# UNO-Rev3_Breakout_v10.net
KiCad netlist of a schematic drawn in EAGLE
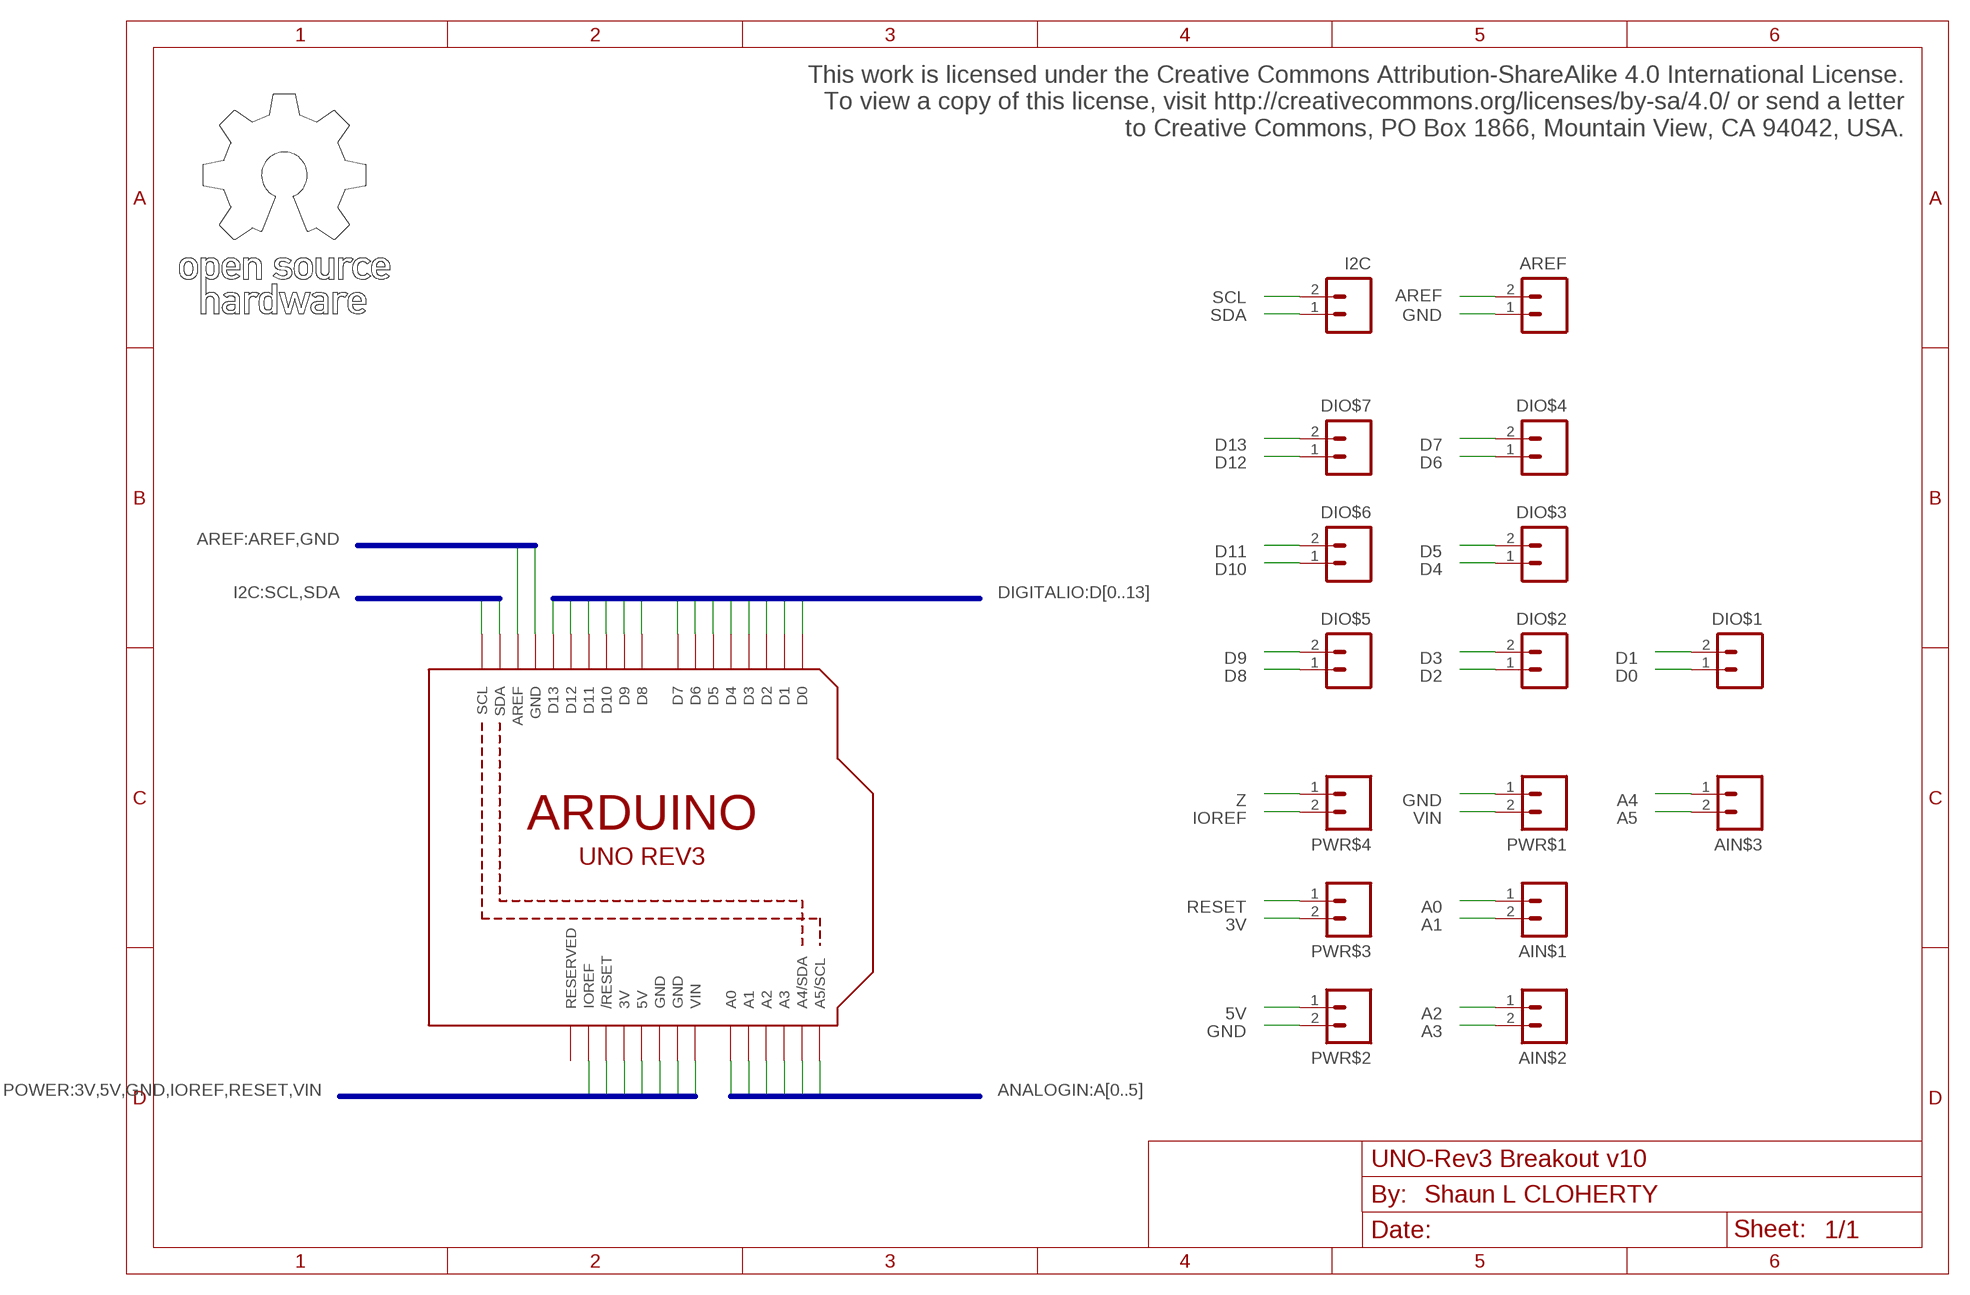
[diagram p0: schematic, sheet 1]

(export (version "E")
  (design (tool "Eeschema 10.0.6"))
  (components
    (comp (ref "AIN$1")
      (value "2-WAY_3.5MM_SCREWTERMINALMINIMAL")
      (footprint "eagle-import:DINKEL-1X2-3.5MMSCREW_MINIMAL")
      (libsource (lib "eagle-import") (part "2-WAY_3.5MM_SCREWTERMINALMINIMAL"))
    )
    (comp (ref "AIN$2")
      (value "2-WAY_3.5MM_SCREWTERMINALMINIMAL")
      (footprint "eagle-import:DINKEL-1X2-3.5MMSCREW_MINIMAL")
      (libsource (lib "eagle-import") (part "2-WAY_3.5MM_SCREWTERMINALMINIMAL"))
    )
    (comp (ref "AIN$3")
      (value "2-WAY_3.5MM_SCREWTERMINALMINIMAL")
      (footprint "eagle-import:DINKEL-1X2-3.5MMSCREW_MINIMAL")
      (libsource (lib "eagle-import") (part "2-WAY_3.5MM_SCREWTERMINALMINIMAL"))
    )
    (comp (ref "AREF")
      (value "2-WAY_3.5MM_SCREWTERMINALMINIMAL")
      (footprint "eagle-import:DINKEL-1X2-3.5MMSCREW_MINIMAL")
      (libsource (lib "eagle-import") (part "2-WAY_3.5MM_SCREWTERMINALMINIMAL"))
    )
    (comp (ref "DIO$1")
      (value "2-WAY_3.5MM_SCREWTERMINALMINIMAL")
      (footprint "eagle-import:DINKEL-1X2-3.5MMSCREW_MINIMAL")
      (libsource (lib "eagle-import") (part "2-WAY_3.5MM_SCREWTERMINALMINIMAL"))
    )
    (comp (ref "DIO$2")
      (value "2-WAY_3.5MM_SCREWTERMINALMINIMAL")
      (footprint "eagle-import:DINKEL-1X2-3.5MMSCREW_MINIMAL")
      (libsource (lib "eagle-import") (part "2-WAY_3.5MM_SCREWTERMINALMINIMAL"))
    )
    (comp (ref "DIO$3")
      (value "2-WAY_3.5MM_SCREWTERMINALMINIMAL")
      (footprint "eagle-import:DINKEL-1X2-3.5MMSCREW_MINIMAL")
      (libsource (lib "eagle-import") (part "2-WAY_3.5MM_SCREWTERMINALMINIMAL"))
    )
    (comp (ref "DIO$4")
      (value "2-WAY_3.5MM_SCREWTERMINALMINIMAL")
      (footprint "eagle-import:DINKEL-1X2-3.5MMSCREW_MINIMAL")
      (libsource (lib "eagle-import") (part "2-WAY_3.5MM_SCREWTERMINALMINIMAL"))
    )
    (comp (ref "DIO$5")
      (value "2-WAY_3.5MM_SCREWTERMINALMINIMAL")
      (footprint "eagle-import:DINKEL-1X2-3.5MMSCREW_MINIMAL")
      (libsource (lib "eagle-import") (part "2-WAY_3.5MM_SCREWTERMINALMINIMAL"))
    )
    (comp (ref "DIO$6")
      (value "2-WAY_3.5MM_SCREWTERMINALMINIMAL")
      (footprint "eagle-import:DINKEL-1X2-3.5MMSCREW_MINIMAL")
      (libsource (lib "eagle-import") (part "2-WAY_3.5MM_SCREWTERMINALMINIMAL"))
    )
    (comp (ref "DIO$7")
      (value "2-WAY_3.5MM_SCREWTERMINALMINIMAL")
      (footprint "eagle-import:DINKEL-1X2-3.5MMSCREW_MINIMAL")
      (libsource (lib "eagle-import") (part "2-WAY_3.5MM_SCREWTERMINALMINIMAL"))
    )
    (comp (ref "I2C")
      (value "2-WAY_3.5MM_SCREWTERMINALMINIMAL")
      (footprint "eagle-import:DINKEL-1X2-3.5MMSCREW_MINIMAL")
      (libsource (lib "eagle-import") (part "2-WAY_3.5MM_SCREWTERMINALMINIMAL"))
    )
    (comp (ref "PWR$1")
      (value "2-WAY_3.5MM_SCREWTERMINALMINIMAL")
      (footprint "eagle-import:DINKEL-1X2-3.5MMSCREW_MINIMAL")
      (libsource (lib "eagle-import") (part "2-WAY_3.5MM_SCREWTERMINALMINIMAL"))
    )
    (comp (ref "PWR$2")
      (value "2-WAY_3.5MM_SCREWTERMINALMINIMAL")
      (footprint "eagle-import:DINKEL-1X2-3.5MMSCREW_MINIMAL")
      (libsource (lib "eagle-import") (part "2-WAY_3.5MM_SCREWTERMINALMINIMAL"))
    )
    (comp (ref "PWR$3")
      (value "2-WAY_3.5MM_SCREWTERMINALMINIMAL")
      (footprint "eagle-import:DINKEL-1X2-3.5MMSCREW_MINIMAL")
      (libsource (lib "eagle-import") (part "2-WAY_3.5MM_SCREWTERMINALMINIMAL"))
    )
    (comp (ref "PWR$4")
      (value "2-WAY_3.5MM_SCREWTERMINALMINIMAL")
      (footprint "eagle-import:DINKEL-1X2-3.5MMSCREW_MINIMAL")
      (libsource (lib "eagle-import") (part "2-WAY_3.5MM_SCREWTERMINALMINIMAL"))
    )
    (comp (ref "U$1")
      (value "ARDUINO-UNO-REV3_SHIELD")
      (footprint "eagle-import:ARDUINOR3_SHORT_NOLABELS")
      (libsource (lib "eagle-import") (part "ARDUINO-UNO-REV3_SHIELD"))
    )
    (comp (ref "U$6")
      (value "OSHW_LOGO")
      (footprint "eagle-import:OSHW_10MM")
      (libsource (lib "eagle-import") (part "OSHW_LOGO"))
    )
  )
  (nets
    (net (code "24") (name "/3V") (class "Default")
      (node (ref "PWR$3") (pin "2") (pinfunction "2_2") (pintype "passive"))
      (node (ref "U$1") (pin "3V") (pinfunction "3V_3V") (pintype "power_in"))
    )
    (net (code "25") (name "/5V") (class "Default")
      (node (ref "PWR$2") (pin "1") (pinfunction "1_1") (pintype "passive"))
      (node (ref "U$1") (pin "5V") (pinfunction "5V_5V") (pintype "power_in"))
    )
    (net (code "26") (name "/A0") (class "Default")
      (node (ref "AIN$1") (pin "1") (pinfunction "1_1") (pintype "passive"))
      (node (ref "U$1") (pin "A0") (pinfunction "A0_A0") (pintype "bidirectional"))
    )
    (net (code "27") (name "/A1") (class "Default")
      (node (ref "AIN$1") (pin "2") (pinfunction "2_2") (pintype "passive"))
      (node (ref "U$1") (pin "A1") (pinfunction "A1_A1") (pintype "bidirectional"))
    )
    (net (code "28") (name "/A2") (class "Default")
      (node (ref "AIN$2") (pin "1") (pinfunction "1_1") (pintype "passive"))
      (node (ref "U$1") (pin "A2") (pinfunction "A2_A2") (pintype "bidirectional"))
    )
    (net (code "29") (name "/A3") (class "Default")
      (node (ref "AIN$2") (pin "2") (pinfunction "2_2") (pintype "passive"))
      (node (ref "U$1") (pin "A3") (pinfunction "A3_A3") (pintype "bidirectional"))
    )
    (net (code "30") (name "/A4") (class "Default")
      (node (ref "AIN$3") (pin "1") (pinfunction "1_1") (pintype "passive"))
      (node (ref "U$1") (pin "A4") (pinfunction "A4/SDA_A4") (pintype "bidirectional"))
    )
    (net (code "31") (name "/A5") (class "Default")
      (node (ref "AIN$3") (pin "2") (pinfunction "2_2") (pintype "passive"))
      (node (ref "U$1") (pin "A5") (pinfunction "A5/SCL_A5") (pintype "bidirectional"))
    )
    (net (code "33") (name "/AREF") (class "Default")
      (node (ref "AREF") (pin "2") (pinfunction "2_2") (pintype "passive"))
      (node (ref "U$1") (pin "AREF") (pinfunction "AREF_AREF") (pintype "bidirectional"))
    )
    (net (code "34") (name "/D0") (class "Default")
      (node (ref "DIO$1") (pin "1") (pinfunction "1_1") (pintype "passive"))
      (node (ref "U$1") (pin "D0") (pinfunction "D0_D0") (pintype "bidirectional"))
    )
    (net (code "35") (name "/D1") (class "Default")
      (node (ref "DIO$1") (pin "2") (pinfunction "2_2") (pintype "passive"))
      (node (ref "U$1") (pin "D1") (pinfunction "D1_D1") (pintype "bidirectional"))
    )
    (net (code "36") (name "/D2") (class "Default")
      (node (ref "DIO$2") (pin "1") (pinfunction "1_1") (pintype "passive"))
      (node (ref "U$1") (pin "D2") (pinfunction "D2_D2") (pintype "bidirectional"))
    )
    (net (code "37") (name "/D3") (class "Default")
      (node (ref "DIO$2") (pin "2") (pinfunction "2_2") (pintype "passive"))
      (node (ref "U$1") (pin "D3") (pinfunction "D3_D3") (pintype "bidirectional"))
    )
    (net (code "38") (name "/D4") (class "Default")
      (node (ref "DIO$3") (pin "1") (pinfunction "1_1") (pintype "passive"))
      (node (ref "U$1") (pin "D4") (pinfunction "D4_D4") (pintype "bidirectional"))
    )
    (net (code "39") (name "/D5") (class "Default")
      (node (ref "DIO$3") (pin "2") (pinfunction "2_2") (pintype "passive"))
      (node (ref "U$1") (pin "D5") (pinfunction "D5_D5") (pintype "bidirectional"))
    )
    (net (code "40") (name "/D6") (class "Default")
      (node (ref "DIO$4") (pin "1") (pinfunction "1_1") (pintype "passive"))
      (node (ref "U$1") (pin "D6") (pinfunction "D6_D6") (pintype "bidirectional"))
    )
    (net (code "41") (name "/D7") (class "Default")
      (node (ref "DIO$4") (pin "2") (pinfunction "2_2") (pintype "passive"))
      (node (ref "U$1") (pin "D7") (pinfunction "D7_D7") (pintype "bidirectional"))
    )
    (net (code "42") (name "/D8") (class "Default")
      (node (ref "DIO$5") (pin "1") (pinfunction "1_1") (pintype "passive"))
      (node (ref "U$1") (pin "D8") (pinfunction "D8_D8") (pintype "bidirectional"))
    )
    (net (code "43") (name "/D9") (class "Default")
      (node (ref "DIO$5") (pin "2") (pinfunction "2_2") (pintype "passive"))
      (node (ref "U$1") (pin "D9") (pinfunction "D9_D9") (pintype "bidirectional"))
    )
    (net (code "44") (name "/D10") (class "Default")
      (node (ref "DIO$6") (pin "1") (pinfunction "1_1") (pintype "passive"))
      (node (ref "U$1") (pin "D10") (pinfunction "D10_D10") (pintype "bidirectional"))
    )
    (net (code "45") (name "/D11") (class "Default")
      (node (ref "DIO$6") (pin "2") (pinfunction "2_2") (pintype "passive"))
      (node (ref "U$1") (pin "D11") (pinfunction "D11_D11") (pintype "bidirectional"))
    )
    (net (code "46") (name "/D12") (class "Default")
      (node (ref "DIO$7") (pin "1") (pinfunction "1_1") (pintype "passive"))
      (node (ref "U$1") (pin "D12") (pinfunction "D12_D12") (pintype "bidirectional"))
    )
    (net (code "47") (name "/D13") (class "Default")
      (node (ref "DIO$7") (pin "2") (pinfunction "2_2") (pintype "passive"))
      (node (ref "U$1") (pin "D13") (pinfunction "D13_D13") (pintype "bidirectional"))
    )
    (net (code "49") (name "/GND") (class "Default")
      (node (ref "AREF") (pin "1") (pinfunction "1_1") (pintype "passive"))
      (node (ref "PWR$1") (pin "1") (pinfunction "1_1") (pintype "passive"))
      (node (ref "PWR$2") (pin "2") (pinfunction "2_2") (pintype "passive"))
      (node (ref "U$1") (pin "GND") (pinfunction "GND_GND") (pintype "power_in"))
      (node (ref "U$1") (pin "GND@1") (pinfunction "GND_GND@1") (pintype "power_in"))
      (node (ref "U$1") (pin "GND@2") (pinfunction "GND_GND@2") (pintype "power_in"))
    )
    (net (code "50") (name "/IOREF") (class "Default")
      (node (ref "PWR$4") (pin "2") (pinfunction "2_2") (pintype "passive"))
      (node (ref "U$1") (pin "IOREF") (pinfunction "IOREF_IOREF") (pintype "output"))
    )
    (net (code "51") (name "/RESET") (class "Default")
      (node (ref "PWR$3") (pin "1") (pinfunction "1_1") (pintype "passive"))
      (node (ref "U$1") (pin "RESET") (pinfunction "/RESET_RESET") (pintype "bidirectional"))
    )
    (net (code "52") (name "/SCL") (class "Default")
      (node (ref "I2C") (pin "2") (pinfunction "2_2") (pintype "passive"))
      (node (ref "U$1") (pin "SCL") (pinfunction "SCL_SCL") (pintype "bidirectional"))
    )
    (net (code "53") (name "/SDA") (class "Default")
      (node (ref "I2C") (pin "1") (pinfunction "1_1") (pintype "passive"))
      (node (ref "U$1") (pin "SDA") (pinfunction "SDA_SDA") (pintype "bidirectional"))
    )
    (net (code "54") (name "/VIN") (class "Default")
      (node (ref "PWR$1") (pin "2") (pinfunction "2_2") (pintype "passive"))
      (node (ref "U$1") (pin "VIN") (pinfunction "VIN_VIN") (pintype "power_in"))
    )
    (net (code "55") (name "/Z") (class "Default")
      (node (ref "PWR$4") (pin "1") (pinfunction "1_1") (pintype "passive"))
    )
    (net (code "59") (name "unconnected-(U$1-PadRESERVED)") (class "Default")
      (node (ref "U$1") (pin "RESERVED") (pinfunction "RESERVED_RESERVED") (pintype "no_connect"))
    )
  )
)
